# Uart_and_Daylight_Sensor.net
KiCad netlist of a schematic drawn in Altium Designer
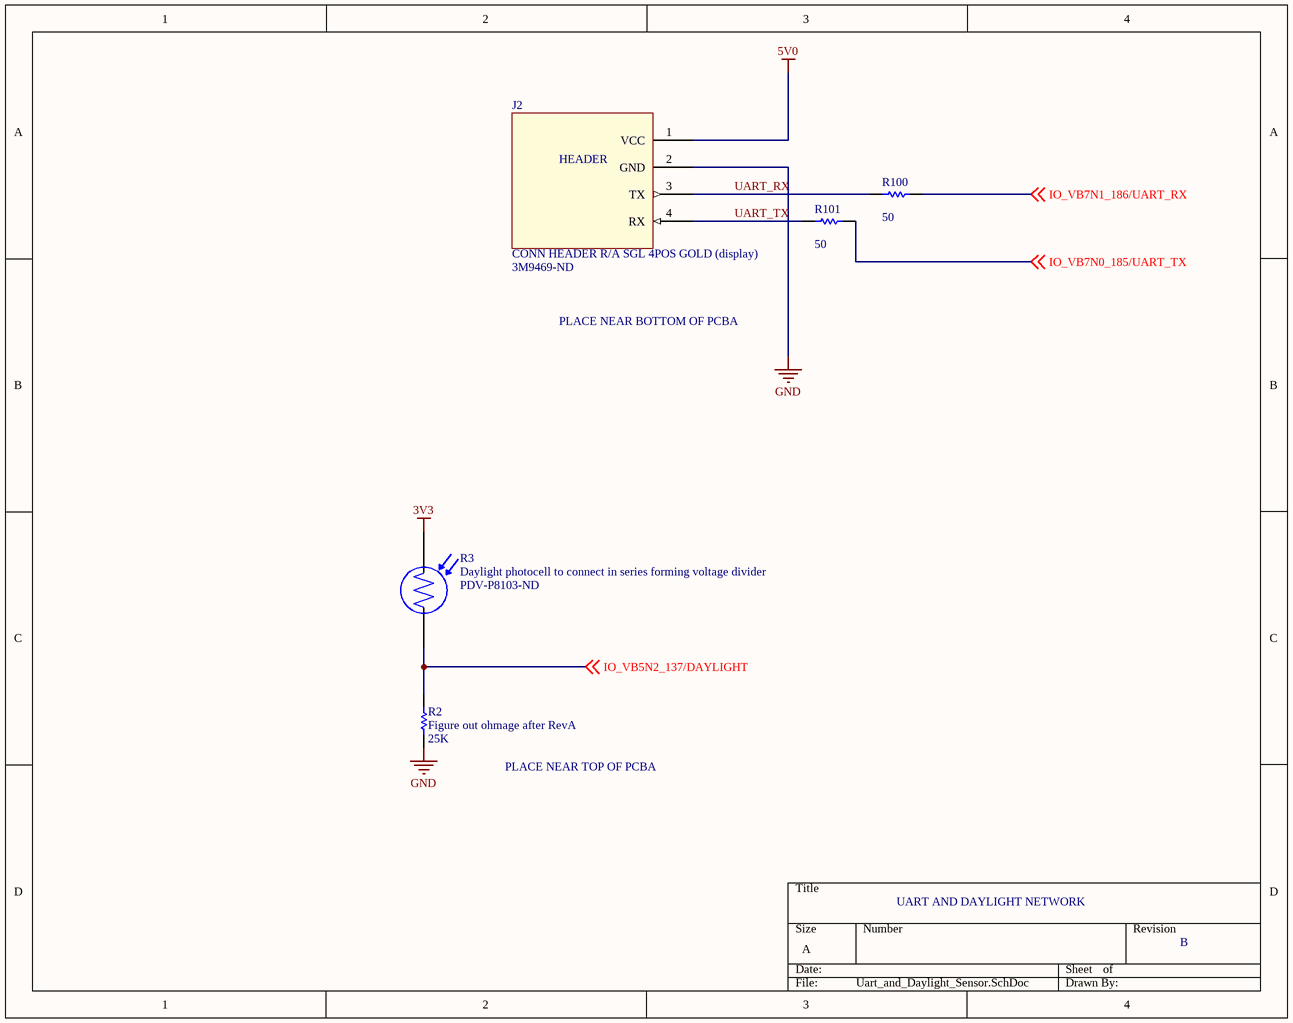
[diagram p0: Uart_and_Daylight_Sensor.SchDoc]

(export (version "E")
  (design (tool "Eeschema 10.0.6"))
  (components
    (comp (ref "J2")
      (value "CONN HEADER R/A SGL 4POS GOLD (display)")
      (footprint "HEADER_4POS_UART")
      (description "http://multimedia.3m.com/mws/media/548122O/3mtm-pin-strip-header-ts2182.pdf")
      (fields (field (name "SUPPLIER PART NUMBER 1") "3M9469-ND"))
      (libsource (lib "schematics") (part "CONN HEADER R/A SGL 4POS GOLD (display)"))
    )
    (comp (ref "R2")
      (value "Figure out ohmage after RevA")
      (footprint "RES_0603")
      (description "Resistor")
      (fields (field (name "ALTIUM_VALUE") "25K") (field (name "PUBLISHER") "Altium Limited"))
      (libsource (lib "Miscellaneous Devices") (part "Res1"))
    )
    (comp (ref "R3")
      (value "Daylight photocell to connect in series forming voltage divider")
      (footprint "RES_NSL-19M51")
      (description "http://media.digikey.com/pdf/Data%20Sheets/Photonic%20Detetectors%20Inc%20PDFs/PDV-P8103.pdf")
      (fields (field (name "SUPPLIER PART NUMBER 1") "PDV-P8103-ND"))
      (libsource (lib "schematics") (part "PHOTOCELL 16-33KOHM"))
    )
    (comp (ref "R100")
      (value "50")
      (footprint "RES_0603")
      (description "Resistor")
      (fields (field (name "Comment") "0R") (field (name "PUBLISHER") "Altium Limited"))
      (libsource (lib "Miscellaneous Devices") (part "Res1"))
    )
    (comp (ref "R101")
      (value "50")
      (footprint "RES_0603")
      (description "Resistor")
      (fields
        (field (name "Comment") "Figure out ohmage after RevA")
        (field (name "PUBLISHER") "Altium Limited")
      )
      (libsource (lib "Miscellaneous Devices") (part "Res1"))
    )
  )
  (nets
    (net (code "1") (name "/UART_RX") (class "Default")
      (node (ref "J2") (pin "3") (pinfunction "TX_3") (pintype "output"))
      (node (ref "R100") (pin "1") (pinfunction "1_1") (pintype "passive"))
    )
    (net (code "2") (name "/UART_TX") (class "Default")
      (node (ref "J2") (pin "4") (pinfunction "RX_4") (pintype "input"))
      (node (ref "R101") (pin "2") (pinfunction "2_2") (pintype "passive"))
    )
    (net (code "3") (name "3V3") (class "Default")
      (node (ref "R3") (pin "1") (pinfunction "1_1") (pintype "passive"))
    )
    (net (code "4") (name "5V0") (class "Default")
      (node (ref "J2") (pin "1") (pinfunction "VCC_1") (pintype "power_in"))
    )
    (net (code "5") (name "GND") (class "Default")
      (node (ref "J2") (pin "2") (pinfunction "GND_2") (pintype "power_in"))
      (node (ref "R2") (pin "1") (pinfunction "1_1") (pintype "passive"))
    )
    (net (code "6") (name "IO_VB5N2_137{slash}DAYLIGHT") (class "Default")
      (node (ref "R2") (pin "2") (pinfunction "2_2") (pintype "passive"))
      (node (ref "R3") (pin "2") (pinfunction "2_2") (pintype "passive"))
    )
    (net (code "7") (name "IO_VB7N0_185{slash}UART_TX") (class "Default")
      (node (ref "R101") (pin "1") (pinfunction "1_1") (pintype "passive"))
    )
    (net (code "8") (name "IO_VB7N1_186{slash}UART_RX") (class "Default")
      (node (ref "R100") (pin "2") (pinfunction "2_2") (pintype "passive"))
    )
  )
)
